# Power.net
KiCad netlist of a schematic drawn in Altium Designer
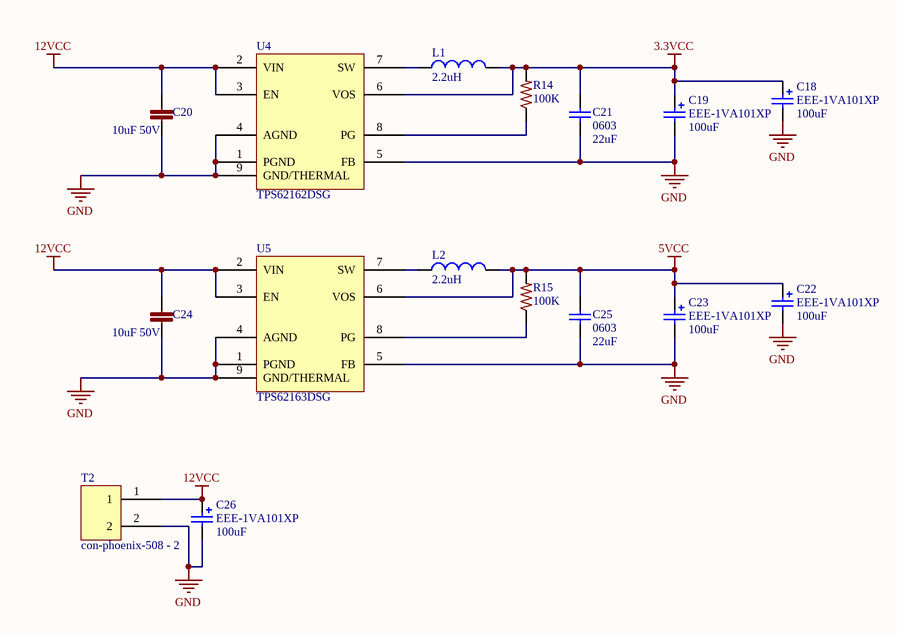
[diagram p0: Power.SchDoc]

(export (version "E")
  (design (tool "Eeschema 10.0.6"))
  (components
    (comp (ref "C18")
      (value "EEE-1VA101XP")
      (footprint "EEE-1VA101XP")
      (description "CAP ALUM 100UF 35V 20% SMD")
      (fields (field (name "DIGIKEY PART #") "PCE3951CT-ND") (field (name "ALTIUM_VALUE") "100uF"))
      (libsource (lib "Tigershark3D") (part "EEE-1VA101XP"))
    )
    (comp (ref "C19")
      (value "EEE-1VA101XP")
      (footprint "EEE-1VA101XP")
      (description "CAP ALUM 100UF 35V 20% SMD")
      (fields (field (name "DIGIKEY PART #") "PCE3951CT-ND") (field (name "ALTIUM_VALUE") "100uF"))
      (libsource (lib "Tigershark3D") (part "EEE-1VA101XP"))
    )
    (comp (ref "C20")
      (value "10uF 50V")
      (footprint "C1206")
      (description "CAP CER 10UF 50V 10% X5R 1206")
      (fields
        (field (name "MANUFACTURER") "Samsung")
        (field (name "MANUFACTURERPARTNUMBER") "CL31A106KBHNNNE")
        (field (name "PUBLISHER") "UltiMachine")
      )
      (libsource (lib "Tigershark3D") (part "CL31A106KBHNNNE"))
    )
    (comp (ref "C21")
      (value "0603")
      (footprint "C0805")
      (description "CAP CER 22UF 6.3V 10% X5R 0805")
      (fields
        (field (name "MFR PART #") "CL21A226KQQNNNE")
        (field (name "MFR") "Samsung")
        (field (name "ALTIUM_VALUE") "22uF")
      )
      (libsource (lib "Sensor Package") (part "CL21A226KQQNNNE"))
    )
    (comp (ref "C22")
      (value "EEE-1VA101XP")
      (footprint "EEE-1VA101XP")
      (description "CAP ALUM 100UF 35V 20% SMD")
      (fields (field (name "DIGIKEY PART #") "PCE3951CT-ND") (field (name "ALTIUM_VALUE") "100uF"))
      (libsource (lib "Tigershark3D") (part "EEE-1VA101XP"))
    )
    (comp (ref "C23")
      (value "EEE-1VA101XP")
      (footprint "EEE-1VA101XP")
      (description "CAP ALUM 100UF 35V 20% SMD")
      (fields (field (name "DIGIKEY PART #") "PCE3951CT-ND") (field (name "ALTIUM_VALUE") "100uF"))
      (libsource (lib "Tigershark3D") (part "EEE-1VA101XP"))
    )
    (comp (ref "C24")
      (value "10uF 50V")
      (footprint "C1206")
      (description "CAP CER 10UF 50V 10% X5R 1206")
      (fields
        (field (name "MANUFACTURER") "Samsung")
        (field (name "MANUFACTURERPARTNUMBER") "CL31A106KBHNNNE")
        (field (name "PUBLISHER") "UltiMachine")
      )
      (libsource (lib "Tigershark3D") (part "CL31A106KBHNNNE"))
    )
    (comp (ref "C25")
      (value "0603")
      (footprint "C0805")
      (description "CAP CER 22UF 6.3V 10% X5R 0805")
      (fields
        (field (name "MFR PART #") "CL21A226KQQNNNE")
        (field (name "MFR") "Samsung")
        (field (name "ALTIUM_VALUE") "22uF")
      )
      (libsource (lib "Sensor Package") (part "CL21A226KQQNNNE"))
    )
    (comp (ref "C26")
      (value "EEE-1VA101XP")
      (footprint "EEE-1VA101XP")
      (description "CAP ALUM 100UF 35V 20% SMD")
      (fields (field (name "DIGIKEY PART #") "PCE3951CT-ND") (field (name "ALTIUM_VALUE") "100uF"))
      (libsource (lib "Tigershark3D") (part "EEE-1VA101XP"))
    )
    (comp (ref "L1")
      (value "2.2uH")
      (footprint "VLS252012T-2R2M1R3")
      (description "VLS252012T-2R2M1R3")
      (fields (field (name "MFR") "TDK Corporation") (field (name "PUBLISHER") "Adam Vadala-Roth"))
      (libsource (lib "Sensor Package") (part "VLS252012T-2R2M1R3"))
    )
    (comp (ref "L2")
      (value "2.2uH")
      (footprint "VLS252012T-2R2M1R3")
      (description "VLS252012T-2R2M1R3")
      (fields (field (name "MFR") "TDK Corporation") (field (name "PUBLISHER") "Adam Vadala-Roth"))
      (libsource (lib "Sensor Package") (part "VLS252012T-2R2M1R3"))
    )
    (comp (ref "R14")
      (value "100K")
      (footprint "R0603")
      (description "RES 100K OHM 1/10W 1% 0603 SMD")
      (fields
        (field (name "MANUFACTURERPARTNUMBER") "RC0603FR-07100KL")
        (field (name "PUBLISHER") "UltiMachine")
      )
      (libsource (lib "3Delight") (part "RC0603FR-07100KL"))
    )
    (comp (ref "R15")
      (value "100K")
      (footprint "R0603")
      (description "RES 100K OHM 1/10W 1% 0603 SMD")
      (fields
        (field (name "MANUFACTURERPARTNUMBER") "RC0603FR-07100KL")
        (field (name "PUBLISHER") "UltiMachine")
      )
      (libsource (lib "3Delight") (part "RC0603FR-07100KL"))
    )
    (comp (ref "T2")
      (value "con-phoenix-508 - 2")
      (footprint "MSTBV2 - duplicate")
      (libsource (lib "ZMBo Schematic Library") (part "con-phoenix-508_2"))
    )
    (comp (ref "U4")
      (value "TPS62162DSG")
      (footprint "DSG8-1600X900TP")
      (libsource (lib "Adams Altium Library") (part "TPS62162SOP"))
    )
    (comp (ref "U5")
      (value "TPS62163DSG")
      (footprint "DSG8-1600X900TP")
      (libsource (lib "Adams Altium Library") (part "TPS62162SOP"))
    )
  )
  (nets
    (net (code "1") (name "3.3VCC") (class "Default")
      (node (ref "C18") (pin "1") (pinfunction "1_1") (pintype "passive"))
      (node (ref "C19") (pin "1") (pinfunction "1_1") (pintype "passive"))
      (node (ref "C21") (pin "2") (pinfunction "2_2") (pintype "passive"))
      (node (ref "L1") (pin "2") (pinfunction "2_2") (pintype "passive"))
      (node (ref "R14") (pin "2") (pinfunction "2_2") (pintype "passive"))
      (node (ref "U4") (pin "6") (pinfunction "VOS_6") (pintype "passive"))
    )
    (net (code "2") (name "5VCC") (class "Default")
      (node (ref "C22") (pin "1") (pinfunction "1_1") (pintype "passive"))
      (node (ref "C23") (pin "1") (pinfunction "1_1") (pintype "passive"))
      (node (ref "C25") (pin "2") (pinfunction "2_2") (pintype "passive"))
      (node (ref "L2") (pin "2") (pinfunction "2_2") (pintype "passive"))
      (node (ref "R15") (pin "2") (pinfunction "2_2") (pintype "passive"))
      (node (ref "U5") (pin "6") (pinfunction "VOS_6") (pintype "passive"))
    )
    (net (code "3") (name "12VCC") (class "Default")
      (node (ref "C20") (pin "1") (pinfunction "1_1") (pintype "passive"))
      (node (ref "C24") (pin "1") (pinfunction "1_1") (pintype "passive"))
      (node (ref "C26") (pin "1") (pinfunction "1_1") (pintype "passive"))
      (node (ref "T2") (pin "1") (pinfunction "1_1") (pintype "passive"))
      (node (ref "U4") (pin "2") (pinfunction "VIN_2") (pintype "passive"))
      (node (ref "U4") (pin "3") (pinfunction "EN_3") (pintype "passive"))
      (node (ref "U5") (pin "2") (pinfunction "VIN_2") (pintype "passive"))
      (node (ref "U5") (pin "3") (pinfunction "EN_3") (pintype "passive"))
    )
    (net (code "4") (name "GND") (class "Default")
      (node (ref "C18") (pin "2") (pinfunction "2_2") (pintype "passive"))
      (node (ref "C19") (pin "2") (pinfunction "2_2") (pintype "passive"))
      (node (ref "C20") (pin "2") (pinfunction "2_2") (pintype "passive"))
      (node (ref "C21") (pin "1") (pinfunction "1_1") (pintype "passive"))
      (node (ref "C22") (pin "2") (pinfunction "2_2") (pintype "passive"))
      (node (ref "C23") (pin "2") (pinfunction "2_2") (pintype "passive"))
      (node (ref "C24") (pin "2") (pinfunction "2_2") (pintype "passive"))
      (node (ref "C25") (pin "1") (pinfunction "1_1") (pintype "passive"))
      (node (ref "C26") (pin "2") (pinfunction "2_2") (pintype "passive"))
      (node (ref "T2") (pin "2") (pinfunction "2_2") (pintype "passive"))
      (node (ref "U4") (pin "1") (pinfunction "PGND_1") (pintype "passive"))
      (node (ref "U4") (pin "4") (pinfunction "AGND_4") (pintype "passive"))
      (node (ref "U4") (pin "5") (pinfunction "FB_5") (pintype "passive"))
      (node (ref "U4") (pin "9") (pinfunction "GND/THERMAL_9") (pintype "passive"))
      (node (ref "U5") (pin "1") (pinfunction "PGND_1") (pintype "passive"))
      (node (ref "U5") (pin "4") (pinfunction "AGND_4") (pintype "passive"))
      (node (ref "U5") (pin "5") (pinfunction "FB_5") (pintype "passive"))
      (node (ref "U5") (pin "9") (pinfunction "GND/THERMAL_9") (pintype "passive"))
    )
    (net (code "5") (name "Net-(U4-PG)") (class "Default")
      (node (ref "R14") (pin "1") (pinfunction "1_1") (pintype "passive"))
      (node (ref "U4") (pin "8") (pinfunction "PG_8") (pintype "passive"))
    )
    (net (code "6") (name "Net-(U4-SW)") (class "Default")
      (node (ref "L1") (pin "1") (pinfunction "1_1") (pintype "passive"))
      (node (ref "U4") (pin "7") (pinfunction "SW_7") (pintype "passive"))
    )
    (net (code "7") (name "Net-(U5-PG)") (class "Default")
      (node (ref "R15") (pin "1") (pinfunction "1_1") (pintype "passive"))
      (node (ref "U5") (pin "8") (pinfunction "PG_8") (pintype "passive"))
    )
    (net (code "8") (name "Net-(U5-SW)") (class "Default")
      (node (ref "L2") (pin "1") (pinfunction "1_1") (pintype "passive"))
      (node (ref "U5") (pin "7") (pinfunction "SW_7") (pintype "passive"))
    )
  )
)
